# ZOWI_Main_Board_Autoreset.net
KiCad netlist of a schematic drawn in Altium Designer
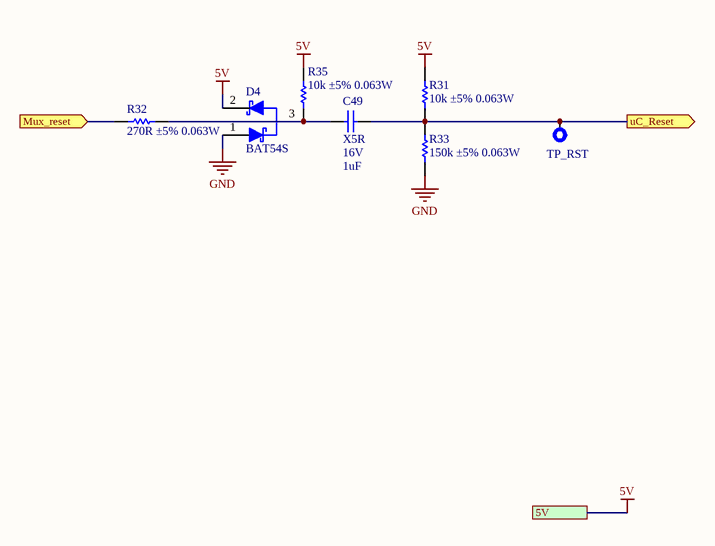
[diagram p0: ZOWI_Main_Board_Autoreset.SchDoc]

(export (version "E")
  (design (tool "Eeschema 10.0.6"))
  (components
    (comp (ref "C49")
      (value "Capacitor")
      (footprint "C0603")
      (description "Capacitor SMD")
      (fields
        (field (name "DIELECTRIC") "X5R")
        (field (name "VOLTAGE") "16V")
        (field (name "CAPACITANCE") "1uF")
        (field (name "PART NUMBER") "C0603_1uF_16V_±10%")
        (field (name "TOLERANCE") "±10%")
      )
      (libsource (lib "Pasives_Capacitor_SMD") (part "Capacitor"))
    )
    (comp (ref "D4")
      (value "BAT54S")
      (footprint "SOT23-3")
      (description "Dual Schottky Diode")
      (fields (field (name "MANUFACTURER") "NXP"))
      (libsource (lib "Semiconductors_Diodes") (part "Dual Schottky"))
    )
    (comp (ref "R31")
      (value "10k ±5% 0.063W")
      (footprint "R0402")
      (description "Resistor, SMD")
      (fields (field (name "TOLERANCE") "±5%") (field (name "POWER") "0.063W"))
      (libsource (lib "Pasives_Resistor_SMD") (part "Resistor"))
    )
    (comp (ref "R32")
      (value "270R ±5% 0.063W")
      (footprint "R0402")
      (description "Resistor, SMD")
      (fields (field (name "TOLERANCE") "±5%") (field (name "POWER") "0.063W"))
      (libsource (lib "Pasives_Resistor_SMD") (part "Resistor"))
    )
    (comp (ref "R33")
      (value "150k ±5% 0.063W")
      (footprint "R0402")
      (description "Resistor, SMD")
      (fields (field (name "TOLERANCE") "±5%") (field (name "POWER") "0.063W"))
      (libsource (lib "Pasives_Resistor_SMD") (part "Resistor"))
    )
    (comp (ref "R35")
      (value "10k ±5% 0.063W")
      (footprint "R0402")
      (description "Resistor, SMD")
      (fields (field (name "TOLERANCE") "±5%") (field (name "POWER") "0.063W"))
      (libsource (lib "Pasives_Resistor_SMD") (part "Resistor"))
    )
    (comp (ref "TP_RST")
      (value "Testpoint")
      (footprint "TP_SMD_1mm")
      (fields (field (name "MANUFACTURER") "Oxley") (field (name "PART NUMBER") "TP_SMD_1mm"))
      (libsource (lib "Miscelanea") (part "Testpoint"))
    )
  )
  (nets
    (net (code "1") (name "/Mux_reset") (class "Default")
      (node (ref "R32") (pin "1") (pinfunction "1_1") (pintype "passive"))
    )
    (net (code "2") (name "/uC_Reset") (class "Default")
      (node (ref "C49") (pin "2") (pinfunction "2_2") (pintype "passive"))
      (node (ref "R31") (pin "1") (pinfunction "1_1") (pintype "passive"))
      (node (ref "R33") (pin "2") (pinfunction "2_2") (pintype "passive"))
      (node (ref "TP_RST") (pin "1") (pinfunction "1_1") (pintype "passive"))
    )
    (net (code "3") (name "5V") (class "Default")
      (node (ref "D4") (pin "2") (pinfunction "K2_2") (pintype "passive"))
      (node (ref "R31") (pin "2") (pinfunction "2_2") (pintype "passive"))
      (node (ref "R35") (pin "2") (pinfunction "2_2") (pintype "passive"))
    )
    (net (code "4") (name "GND") (class "Default")
      (node (ref "D4") (pin "1") (pinfunction "A_1") (pintype "passive"))
      (node (ref "R33") (pin "1") (pinfunction "1_1") (pintype "passive"))
    )
    (net (code "5") (name "Net-(D4-K1)") (class "Default")
      (node (ref "C49") (pin "1") (pinfunction "1_1") (pintype "passive"))
      (node (ref "D4") (pin "3") (pinfunction "K1_3") (pintype "passive"))
      (node (ref "R32") (pin "2") (pinfunction "2_2") (pintype "passive"))
      (node (ref "R35") (pin "1") (pinfunction "1_1") (pintype "passive"))
    )
  )
)
